# LTC.net
KiCad netlist of a schematic drawn in Altium Designer
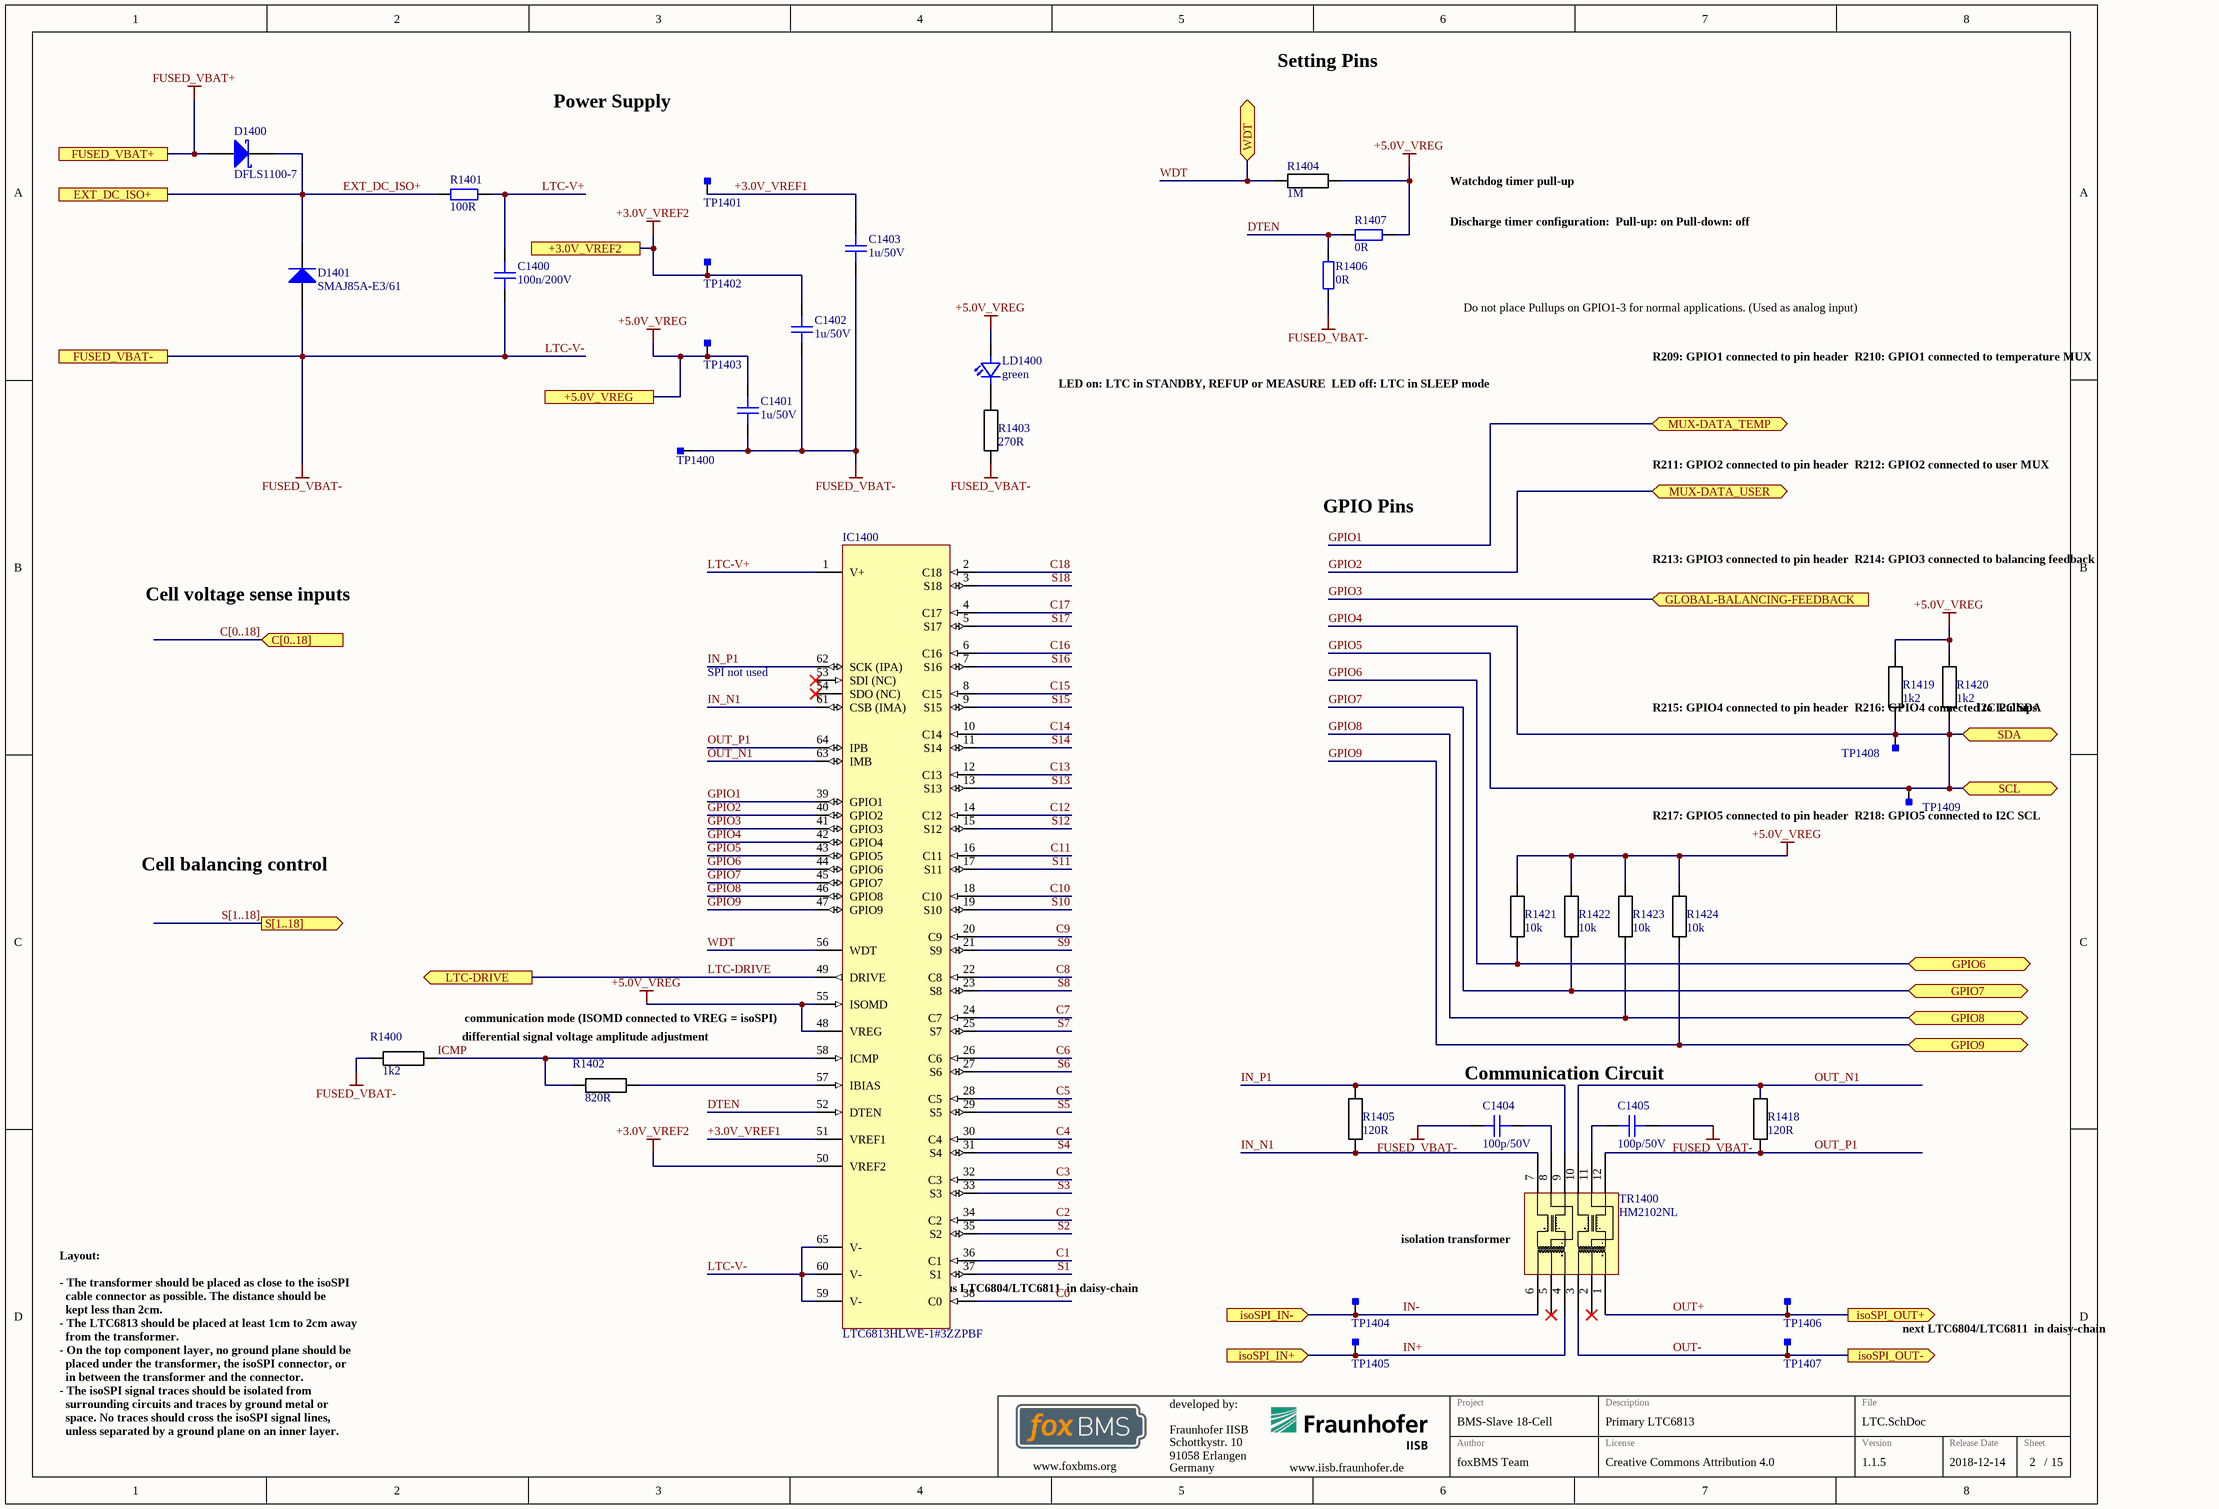
[diagram p0: LTC.SchDoc]

(export (version "E")
  (design (tool "Eeschema 10.0.6"))
  (components
    (comp (ref "C1400")
      (value "100n/200V")
      (footprint "CAPC3216X18N")
      (description "MLCC")
      (fields (field (name "PART NUMBER") "gen_C_ceramic_100n_200V_X7R_1206"))
      (libsource (lib "OE750") (part "C"))
    )
    (comp (ref "C1401")
      (value "1u/50V")
      (footprint "CAPC2012X14N")
      (description "MLCC")
      (fields (field (name "PART NUMBER") "gen_C_ceramic_1u_50V_X7R_0805") (field (name "TOLERANCE") "± 10%"))
      (libsource (lib "OE750") (part "C"))
    )
    (comp (ref "C1402")
      (value "1u/50V")
      (footprint "CAPC2012X14N")
      (description "MLCC")
      (fields (field (name "PART NUMBER") "gen_C_ceramic_1u_50V_X7R_0805") (field (name "TOLERANCE") "± 10%"))
      (libsource (lib "OE750") (part "C"))
    )
    (comp (ref "C1403")
      (value "1u/50V")
      (footprint "CAPC2012X14N")
      (description "MLCC")
      (fields (field (name "PART NUMBER") "gen_C_ceramic_1u_50V_X7R_0805") (field (name "TOLERANCE") "± 10%"))
      (libsource (lib "OE750") (part "C"))
    )
    (comp (ref "C1404")
      (value "100p/50V")
      (footprint "CAPC1608X08N")
      (description "MLCC")
      (fields
        (field (name "PART NUMBER") "gen_C_ceramic_100p_50V_C0G_0603")
        (field (name "TOLERANCE") "± 10%")
      )
      (libsource (lib "OE750") (part "C"))
    )
    (comp (ref "C1405")
      (value "100p/50V")
      (footprint "CAPC1608X08N")
      (description "MLCC")
      (fields
        (field (name "PART NUMBER") "gen_C_ceramic_100p_50V_C0G_0603")
        (field (name "TOLERANCE") "± 10%")
      )
      (libsource (lib "OE750") (part "C"))
    )
    (comp (ref "D1400")
      (value "DFLS1100-7")
      (footprint "DIOD-POWERDI123-2_V")
      (fields (field (name "MANUFACTURER") "Diodes Inc"))
      (libsource (lib "Altium Content Vault") (part "DSKY-AK-2"))
    )
    (comp (ref "D1401")
      (value "SMAJ85A-E3/61")
      (footprint "VISH-DO-214AC-2_L")
      (fields (field (name "MANUFACTURER") "Vishay Semiconductor"))
      (libsource (lib "Altium Content Vault") (part "VISH-K1A2-2"))
    )
    (comp (ref "IC1400")
      (value "LTC6813HLWE-1#3ZZPBF")
      (footprint "TSQFP50P1200X1200X160_HS-65N")
      (description "18 Cell Multicell Battery Monitor, -40 to 125 degC, Pb-Free")
      (fields (field (name "PARTNUMBER") "LTC6811HG-1#PBF") (field (name "MANUFACTURER") "Linear Technology"))
      (libsource (lib "OE750") (part "LTC6813HLWE-1#3ZZPBF"))
    )
    (comp (ref "LD1400")
      (value "green")
      (footprint "LEDC1608X07N")
      (description "TLMG1100-GS08")
      (fields (field (name "PART NUMBER") "LED_0603_green_AECQ") (field (name "MANUFACTURER") "Vishay"))
      (libsource (lib "OE750") (part "D_LED"))
    )
    (comp (ref "R1400")
      (value "1k2")
      (footprint "RESISTOR 1005 REFLOW")
      (description "Resistor 0603 1k2 0.1W")
      (libsource (lib "Resistor") (part "Resistor"))
    )
    (comp (ref "R1401")
      (value "100R")
      (footprint "RESC2012X05N")
      (description "SMD Resistor 100R 0805")
      (fields (field (name "PART NUMBER") "gen_R_100R_0805") (field (name "TOLERANCE") "1%"))
      (libsource (lib "OE750") (part "R"))
    )
    (comp (ref "R1402")
      (value "820R")
      (footprint "RESISTOR 1005 REFLOW")
      (description "Resistor 0603 820R 0.1W")
      (libsource (lib "Resistor") (part "Resistor"))
    )
    (comp (ref "R1403")
      (value "270R")
      (footprint "RESISTOR 0603 REFLOW")
      (description "Resistor 0603 270R 0.1W")
      (libsource (lib "Resistor") (part "Resistor"))
    )
    (comp (ref "R1404")
      (value "1M")
      (footprint "RESISTOR 0603 REFLOW")
      (description "Resistor 0603 1M 0.1W")
      (libsource (lib "Resistor") (part "Resistor"))
    )
    (comp (ref "R1405")
      (value "120R")
      (footprint "RESISTOR 0603 REFLOW")
      (description "Resistor 0603 120R 0.1W")
      (libsource (lib "Resistor") (part "Resistor"))
    )
    (comp (ref "R1406")
      (value "0R")
      (footprint "RESC1608X05N")
      (description "SMD Resistor 0R 0603")
      (fields (field (name "PART NUMBER") "gen_R_0R_0603") (field (name "POWER") "0.1W"))
      (libsource (lib "OE750") (part "R"))
    )
    (comp (ref "R1407")
      (value "0R")
      (footprint "RESC1608X05N")
      (description "SMD Resistor 0R 0603")
      (fields (field (name "PART NUMBER") "gen_R_0R_0603") (field (name "POWER") "0.1W"))
      (libsource (lib "OE750") (part "R"))
    )
    (comp (ref "R1418")
      (value "120R")
      (footprint "RESISTOR 0603 REFLOW")
      (description "Resistor 0603 120R 0.1W")
      (libsource (lib "Resistor") (part "Resistor"))
    )
    (comp (ref "R1419")
      (value "1k2")
      (footprint "RESISTOR 0603 REFLOW")
      (description "Resistor 0603 1k2 0.1W")
      (libsource (lib "Resistor") (part "Resistor"))
    )
    (comp (ref "R1420")
      (value "1k2")
      (footprint "RESISTOR 0603 REFLOW")
      (description "Resistor 0603 1k2 0.1W")
      (libsource (lib "Resistor") (part "Resistor"))
    )
    (comp (ref "R1421")
      (value "10k")
      (footprint "RESISTOR 0603 REFLOW")
      (description "Resistor 0603 10k 0.1W")
      (libsource (lib "Resistor") (part "Resistor"))
    )
    (comp (ref "R1422")
      (value "10k")
      (footprint "RESISTOR 0603 REFLOW")
      (description "Resistor 0603 10k 0.1W")
      (libsource (lib "Resistor") (part "Resistor"))
    )
    (comp (ref "R1423")
      (value "10k")
      (footprint "RESISTOR 0603 REFLOW")
      (description "Resistor 0603 10k 0.1W")
      (libsource (lib "Resistor") (part "Resistor"))
    )
    (comp (ref "R1424")
      (value "10k")
      (footprint "RESISTOR 0603 REFLOW")
      (description "Resistor 0603 10k 0.1W")
      (libsource (lib "Resistor") (part "Resistor"))
    )
    (comp (ref "TP1400")
      (value "Testpoint_Square")
      (footprint "Testpoint_S1")
      (description "Testpoint, square")
      (libsource (lib "OE750") (part "Testpoint_Square"))
    )
    (comp (ref "TP1401")
      (value "Testpoint_Square")
      (footprint "Testpoint_S1")
      (description "Testpoint, square")
      (libsource (lib "OE750") (part "Testpoint_Square"))
    )
    (comp (ref "TP1402")
      (value "Testpoint_Square")
      (footprint "Testpoint_S1")
      (description "Testpoint, square")
      (libsource (lib "OE750") (part "Testpoint_Square"))
    )
    (comp (ref "TP1403")
      (value "Testpoint_Square")
      (footprint "Testpoint_S1")
      (description "Testpoint, square")
      (libsource (lib "OE750") (part "Testpoint_Square"))
    )
    (comp (ref "TP1404")
      (value "Testpoint_Square")
      (footprint "Testpoint_S1")
      (description "Testpoint, square")
      (libsource (lib "OE750") (part "Testpoint_Square"))
    )
    (comp (ref "TP1405")
      (value "Testpoint_Square")
      (footprint "Testpoint_S1")
      (description "Testpoint, square")
      (libsource (lib "OE750") (part "Testpoint_Square"))
    )
    (comp (ref "TP1406")
      (value "Testpoint_Square")
      (footprint "Testpoint_S1")
      (description "Testpoint, square")
      (libsource (lib "OE750") (part "Testpoint_Square"))
    )
    (comp (ref "TP1407")
      (value "Testpoint_Square")
      (footprint "Testpoint_S1")
      (description "Testpoint, square")
      (libsource (lib "OE750") (part "Testpoint_Square"))
    )
    (comp (ref "TP1408")
      (value "Testpoint_Square")
      (footprint "Testpoint_S1")
      (description "Testpoint, square")
      (libsource (lib "OE750") (part "Testpoint_Square"))
    )
    (comp (ref "TP1409")
      (value "Testpoint_Square")
      (footprint "Testpoint_S1")
      (description "Testpoint, square")
      (libsource (lib "OE750") (part "Testpoint_Square"))
    )
    (comp (ref "TR1400")
      (value "HM2102NL")
      (footprint "HM2102NL")
      (description "Pulse HM2102NL BMS Transformer")
      (fields (field (name "MANUFACTURER") "Pulse"))
      (libsource (lib "OE750") (part "HM2102NL"))
    )
  )
  (nets
    (net (code "1") (name "+3.0V_VREF2") (class "Default")
      (node (ref "C1402") (pin "2") (pinfunction "2_2") (pintype "passive"))
      (node (ref "IC1400") (pin "50") (pinfunction "VREF2_50") (pintype "passive"))
      (node (ref "TP1402") (pin "1") (pinfunction "1_1") (pintype "passive"))
    )
    (net (code "2") (name "+5.0V_VREG") (class "Default")
      (node (ref "C1401") (pin "2") (pinfunction "2_2") (pintype "passive"))
      (node (ref "IC1400") (pin "48") (pinfunction "VREG_48") (pintype "power_in"))
      (node (ref "IC1400") (pin "55") (pinfunction "ISOMD_55") (pintype "input"))
      (node (ref "LD1400") (pin "2") (pinfunction "A_2") (pintype "passive"))
      (node (ref "R1404") (pin "2") (pinfunction "2_2") (pintype "passive"))
      (node (ref "R1407") (pin "2") (pinfunction "2_2") (pintype "passive"))
      (node (ref "R1419") (pin "2") (pinfunction "2_2") (pintype "passive"))
      (node (ref "R1420") (pin "2") (pinfunction "2_2") (pintype "passive"))
      (node (ref "R1421") (pin "2") (pinfunction "2_2") (pintype "passive"))
      (node (ref "R1422") (pin "2") (pinfunction "2_2") (pintype "passive"))
      (node (ref "R1423") (pin "2") (pinfunction "2_2") (pintype "passive"))
      (node (ref "R1424") (pin "2") (pinfunction "2_2") (pintype "passive"))
      (node (ref "TP1403") (pin "1") (pinfunction "1_1") (pintype "passive"))
    )
    (net (code "3") (name "/+3.0V_VREF1") (class "Default")
      (node (ref "C1403") (pin "2") (pinfunction "2_2") (pintype "passive"))
      (node (ref "IC1400") (pin "51") (pinfunction "VREF1_51") (pintype "passive"))
      (node (ref "TP1401") (pin "1") (pinfunction "1_1") (pintype "passive"))
    )
    (net (code "4") (name "/C0") (class "Default")
      (node (ref "IC1400") (pin "38") (pinfunction "C0_38") (pintype "input"))
    )
    (net (code "5") (name "/C1") (class "Default")
      (node (ref "IC1400") (pin "36") (pinfunction "C1_36") (pintype "input"))
    )
    (net (code "6") (name "/C2") (class "Default")
      (node (ref "IC1400") (pin "34") (pinfunction "C2_34") (pintype "input"))
    )
    (net (code "7") (name "/C3") (class "Default")
      (node (ref "IC1400") (pin "32") (pinfunction "C3_32") (pintype "input"))
    )
    (net (code "8") (name "/C4") (class "Default")
      (node (ref "IC1400") (pin "30") (pinfunction "C4_30") (pintype "input"))
    )
    (net (code "9") (name "/C5") (class "Default")
      (node (ref "IC1400") (pin "28") (pinfunction "C5_28") (pintype "input"))
    )
    (net (code "10") (name "/C6") (class "Default")
      (node (ref "IC1400") (pin "26") (pinfunction "C6_26") (pintype "input"))
    )
    (net (code "11") (name "/C7") (class "Default")
      (node (ref "IC1400") (pin "24") (pinfunction "C7_24") (pintype "input"))
    )
    (net (code "12") (name "/C8") (class "Default")
      (node (ref "IC1400") (pin "22") (pinfunction "C8_22") (pintype "input"))
    )
    (net (code "13") (name "/C9") (class "Default")
      (node (ref "IC1400") (pin "20") (pinfunction "C9_20") (pintype "input"))
    )
    (net (code "14") (name "/C10") (class "Default")
      (node (ref "IC1400") (pin "18") (pinfunction "C10_18") (pintype "input"))
    )
    (net (code "15") (name "/C11") (class "Default")
      (node (ref "IC1400") (pin "16") (pinfunction "C11_16") (pintype "input"))
    )
    (net (code "16") (name "/C12") (class "Default")
      (node (ref "IC1400") (pin "14") (pinfunction "C12_14") (pintype "input"))
    )
    (net (code "17") (name "/C13") (class "Default")
      (node (ref "IC1400") (pin "12") (pinfunction "C13_12") (pintype "input"))
    )
    (net (code "18") (name "/C14") (class "Default")
      (node (ref "IC1400") (pin "10") (pinfunction "C14_10") (pintype "input"))
    )
    (net (code "19") (name "/C15") (class "Default")
      (node (ref "IC1400") (pin "8") (pinfunction "C15_8") (pintype "input"))
    )
    (net (code "20") (name "/C16") (class "Default")
      (node (ref "IC1400") (pin "6") (pinfunction "C16_6") (pintype "input"))
    )
    (net (code "21") (name "/C17") (class "Default")
      (node (ref "IC1400") (pin "4") (pinfunction "C17_4") (pintype "input"))
    )
    (net (code "22") (name "/C18") (class "Default")
      (node (ref "IC1400") (pin "2") (pinfunction "C18_2") (pintype "input"))
    )
    (net (code "24") (name "/DTEN") (class "Default")
      (node (ref "IC1400") (pin "52") (pinfunction "DTEN_52") (pintype "input"))
      (node (ref "R1406") (pin "2") (pinfunction "2_2") (pintype "passive"))
      (node (ref "R1407") (pin "1") (pinfunction "1_1") (pintype "passive"))
    )
    (net (code "25") (name "/EXT_DC_ISO+") (class "Default")
      (node (ref "D1400") (pin "2") (pinfunction "K_2") (pintype "passive"))
      (node (ref "D1401") (pin "1") (pinfunction "K_1") (pintype "passive"))
      (node (ref "R1401") (pin "1") (pinfunction "1_1") (pintype "passive"))
    )
    (net (code "26") (name "/GPIO1") (class "Default")
      (node (ref "IC1400") (pin "39") (pinfunction "GPIO1_39") (pintype "bidirectional"))
    )
    (net (code "27") (name "/GPIO2") (class "Default")
      (node (ref "IC1400") (pin "40") (pinfunction "GPIO2_40") (pintype "bidirectional"))
    )
    (net (code "28") (name "/GPIO3") (class "Default")
      (node (ref "IC1400") (pin "41") (pinfunction "GPIO3_41") (pintype "bidirectional"))
    )
    (net (code "29") (name "/GPIO4") (class "Default")
      (node (ref "IC1400") (pin "42") (pinfunction "GPIO4_42") (pintype "bidirectional"))
      (node (ref "IC1400") (pin "43") (pinfunction "GPIO5_43") (pintype "bidirectional"))
      (node (ref "R1419") (pin "1") (pinfunction "1_1") (pintype "passive"))
      (node (ref "R1420") (pin "1") (pinfunction "1_1") (pintype "passive"))
      (node (ref "TP1408") (pin "1") (pinfunction "1_1") (pintype "passive"))
      (node (ref "TP1409") (pin "1") (pinfunction "1_1") (pintype "passive"))
    )
    (net (code "30") (name "/GPIO6") (class "Default")
      (node (ref "IC1400") (pin "44") (pinfunction "GPIO6_44") (pintype "bidirectional"))
      (node (ref "R1421") (pin "1") (pinfunction "1_1") (pintype "passive"))
    )
    (net (code "31") (name "/GPIO7") (class "Default")
      (node (ref "IC1400") (pin "45") (pinfunction "GPIO7_45") (pintype "bidirectional"))
      (node (ref "R1422") (pin "1") (pinfunction "1_1") (pintype "passive"))
    )
    (net (code "32") (name "/GPIO8") (class "Default")
      (node (ref "IC1400") (pin "46") (pinfunction "GPIO8_46") (pintype "bidirectional"))
      (node (ref "R1423") (pin "1") (pinfunction "1_1") (pintype "passive"))
    )
    (net (code "33") (name "/GPIO9") (class "Default")
      (node (ref "IC1400") (pin "47") (pinfunction "GPIO9_47") (pintype "bidirectional"))
      (node (ref "R1424") (pin "1") (pinfunction "1_1") (pintype "passive"))
    )
    (net (code "34") (name "/ICMP") (class "Default")
      (node (ref "IC1400") (pin "58") (pinfunction "ICMP_58") (pintype "input"))
      (node (ref "R1400") (pin "2") (pinfunction "2_2") (pintype "passive"))
      (node (ref "R1402") (pin "1") (pinfunction "1_1") (pintype "passive"))
    )
    (net (code "35") (name "/IN+") (class "Default")
      (node (ref "TP1405") (pin "1") (pinfunction "1_1") (pintype "passive"))
      (node (ref "TR1400") (pin "4") (pintype "passive"))
    )
    (net (code "36") (name "/IN-") (class "Default")
      (node (ref "TP1404") (pin "1") (pinfunction "1_1") (pintype "passive"))
      (node (ref "TR1400") (pin "6") (pintype "passive"))
    )
    (net (code "37") (name "/IN_N1") (class "Default")
      (node (ref "IC1400") (pin "61") (pinfunction "CSB_(IMA)_61") (pintype "bidirectional"))
      (node (ref "R1405") (pin "1") (pinfunction "1_1") (pintype "passive"))
      (node (ref "TR1400") (pin "7") (pintype "passive"))
    )
    (net (code "38") (name "/IN_P1") (class "Default")
      (node (ref "IC1400") (pin "62") (pinfunction "SCK_(IPA)_62") (pintype "bidirectional"))
      (node (ref "R1405") (pin "2") (pinfunction "2_2") (pintype "passive"))
      (node (ref "TR1400") (pin "9") (pintype "passive"))
    )
    (net (code "39") (name "/LTC-DRIVE") (class "Default")
      (node (ref "IC1400") (pin "49") (pinfunction "DRIVE_49") (pintype "output"))
    )
    (net (code "40") (name "/LTC-V+") (class "Default")
      (node (ref "C1400") (pin "1") (pinfunction "1_1") (pintype "passive"))
      (node (ref "IC1400") (pin "1") (pinfunction "V+_1") (pintype "power_in"))
      (node (ref "R1401") (pin "2") (pinfunction "2_2") (pintype "passive"))
    )
    (net (code "41") (name "/OUT+") (class "Default")
      (node (ref "TP1406") (pin "1") (pinfunction "1_1") (pintype "passive"))
      (node (ref "TR1400") (pin "1") (pintype "passive"))
    )
    (net (code "42") (name "/OUT-") (class "Default")
      (node (ref "TP1407") (pin "1") (pinfunction "1_1") (pintype "passive"))
      (node (ref "TR1400") (pin "3") (pintype "passive"))
    )
    (net (code "43") (name "/OUT_N1") (class "Default")
      (node (ref "IC1400") (pin "63") (pinfunction "IMB_63") (pintype "bidirectional"))
      (node (ref "R1418") (pin "2") (pinfunction "2_2") (pintype "passive"))
      (node (ref "TR1400") (pin "10") (pintype "passive"))
    )
    (net (code "44") (name "/OUT_P1") (class "Default")
      (node (ref "IC1400") (pin "64") (pinfunction "IPB_64") (pintype "bidirectional"))
      (node (ref "R1418") (pin "1") (pinfunction "1_1") (pintype "passive"))
      (node (ref "TR1400") (pin "12") (pintype "passive"))
    )
    (net (code "45") (name "/S1") (class "Default")
      (node (ref "IC1400") (pin "37") (pinfunction "S1_37") (pintype "bidirectional"))
    )
    (net (code "46") (name "/S2") (class "Default")
      (node (ref "IC1400") (pin "35") (pinfunction "S2_35") (pintype "bidirectional"))
    )
    (net (code "47") (name "/S3") (class "Default")
      (node (ref "IC1400") (pin "33") (pinfunction "S3_33") (pintype "bidirectional"))
    )
    (net (code "48") (name "/S4") (class "Default")
      (node (ref "IC1400") (pin "31") (pinfunction "S4_31") (pintype "bidirectional"))
    )
    (net (code "49") (name "/S5") (class "Default")
      (node (ref "IC1400") (pin "29") (pinfunction "S5_29") (pintype "bidirectional"))
    )
    (net (code "50") (name "/S6") (class "Default")
      (node (ref "IC1400") (pin "27") (pinfunction "S6_27") (pintype "bidirectional"))
    )
    (net (code "51") (name "/S7") (class "Default")
      (node (ref "IC1400") (pin "25") (pinfunction "S7_25") (pintype "bidirectional"))
    )
    (net (code "52") (name "/S8") (class "Default")
      (node (ref "IC1400") (pin "23") (pinfunction "S8_23") (pintype "bidirectional"))
    )
    (net (code "53") (name "/S9") (class "Default")
      (node (ref "IC1400") (pin "21") (pinfunction "S9_21") (pintype "bidirectional"))
    )
    (net (code "54") (name "/S10") (class "Default")
      (node (ref "IC1400") (pin "19") (pinfunction "S10_19") (pintype "bidirectional"))
    )
    (net (code "55") (name "/S11") (class "Default")
      (node (ref "IC1400") (pin "17") (pinfunction "S11_17") (pintype "bidirectional"))
    )
    (net (code "56") (name "/S12") (class "Default")
      (node (ref "IC1400") (pin "15") (pinfunction "S12_15") (pintype "bidirectional"))
    )
    (net (code "57") (name "/S13") (class "Default")
      (node (ref "IC1400") (pin "13") (pinfunction "S13_13") (pintype "bidirectional"))
    )
    (net (code "58") (name "/S14") (class "Default")
      (node (ref "IC1400") (pin "11") (pinfunction "S14_11") (pintype "bidirectional"))
    )
    (net (code "59") (name "/S15") (class "Default")
      (node (ref "IC1400") (pin "9") (pinfunction "S15_9") (pintype "bidirectional"))
    )
    (net (code "60") (name "/S16") (class "Default")
      (node (ref "IC1400") (pin "7") (pinfunction "S16_7") (pintype "bidirectional"))
    )
    (net (code "61") (name "/S17") (class "Default")
      (node (ref "IC1400") (pin "5") (pinfunction "S17_5") (pintype "bidirectional"))
    )
    (net (code "62") (name "/S18") (class "Default")
      (node (ref "IC1400") (pin "3") (pinfunction "S18_3") (pintype "bidirectional"))
    )
    (net (code "64") (name "/WDT") (class "Default")
      (node (ref "IC1400") (pin "56") (pinfunction "WDT_56") (pintype "tri_state"))
      (node (ref "R1404") (pin "1") (pinfunction "1_1") (pintype "passive"))
    )
    (net (code "65") (name "FUSED_VBAT+") (class "Default")
      (node (ref "D1400") (pin "1") (pinfunction "A_1") (pintype "passive"))
    )
    (net (code "66") (name "FUSED_VBAT-") (class "Default")
      (node (ref "C1400") (pin "2") (pinfunction "2_2") (pintype "passive"))
      (node (ref "C1401") (pin "1") (pinfunction "1_1") (pintype "passive"))
      (node (ref "C1402") (pin "1") (pinfunction "1_1") (pintype "passive"))
      (node (ref "C1403") (pin "1") (pinfunction "1_1") (pintype "passive"))
      (node (ref "C1404") (pin "1") (pinfunction "1_1") (pintype "passive"))
      (node (ref "C1405") (pin "1") (pinfunction "1_1") (pintype "passive"))
      (node (ref "D1401") (pin "2") (pinfunction "A_2") (pintype "passive"))
      (node (ref "IC1400") (pin "59") (pinfunction "V-_59") (pintype "power_in"))
      (node (ref "IC1400") (pin "60") (pinfunction "V-_60") (pintype "power_in"))
      (node (ref "IC1400") (pin "65") (pinfunction "V-_65") (pintype "power_in"))
      (node (ref "R1400") (pin "1") (pinfunction "1_1") (pintype "passive"))
      (node (ref "R1403") (pin "1") (pinfunction "1_1") (pintype "passive"))
      (node (ref "R1406") (pin "1") (pinfunction "1_1") (pintype "passive"))
      (node (ref "TP1400") (pin "1") (pinfunction "1_1") (pintype "passive"))
    )
    (net (code "67") (name "Net-(C1404-Pad2)") (class "Default")
      (node (ref "C1404") (pin "2") (pinfunction "2_2") (pintype "passive"))
      (node (ref "TR1400") (pin "8") (pintype "passive"))
    )
    (net (code "68") (name "Net-(C1405-Pad2)") (class "Default")
      (node (ref "C1405") (pin "2") (pinfunction "2_2") (pintype "passive"))
      (node (ref "TR1400") (pin "11") (pintype "passive"))
    )
    (net (code "69") (name "Net-(IC1400-IBIAS)") (class "Default")
      (node (ref "IC1400") (pin "57") (pinfunction "IBIAS_57") (pintype "input"))
      (node (ref "R1402") (pin "2") (pinfunction "2_2") (pintype "passive"))
    )
    (net (code "70") (name "Net-(LD1400-C)") (class "Default")
      (node (ref "LD1400") (pin "1") (pinfunction "C_1") (pintype "passive"))
      (node (ref "R1403") (pin "2") (pinfunction "2_2") (pintype "passive"))
    )
    (net (code "71") (name "unconnected-(IC1400-SDI_(NC)-Pad53)") (class "Default")
      (node (ref "IC1400") (pin "53") (pinfunction "SDI_(NC)_53") (pintype "input+no_connect"))
    )
    (net (code "72") (name "unconnected-(IC1400-SDO_(NC)-Pad54)") (class "Default")
      (node (ref "IC1400") (pin "54") (pinfunction "SDO_(NC)_54") (pintype "open_collector+no_connect"))
    )
    (net (code "73") (name "unconnected-(TR1400-Pad2)") (class "Default")
      (node (ref "TR1400") (pin "2") (pintype "passive+no_connect"))
    )
    (net (code "74") (name "unconnected-(TR1400-Pad5)") (class "Default")
      (node (ref "TR1400") (pin "5") (pintype "passive+no_connect"))
    )
  )
)
